# untitled.net
KiCad netlist of a schematic drawn in EAGLE
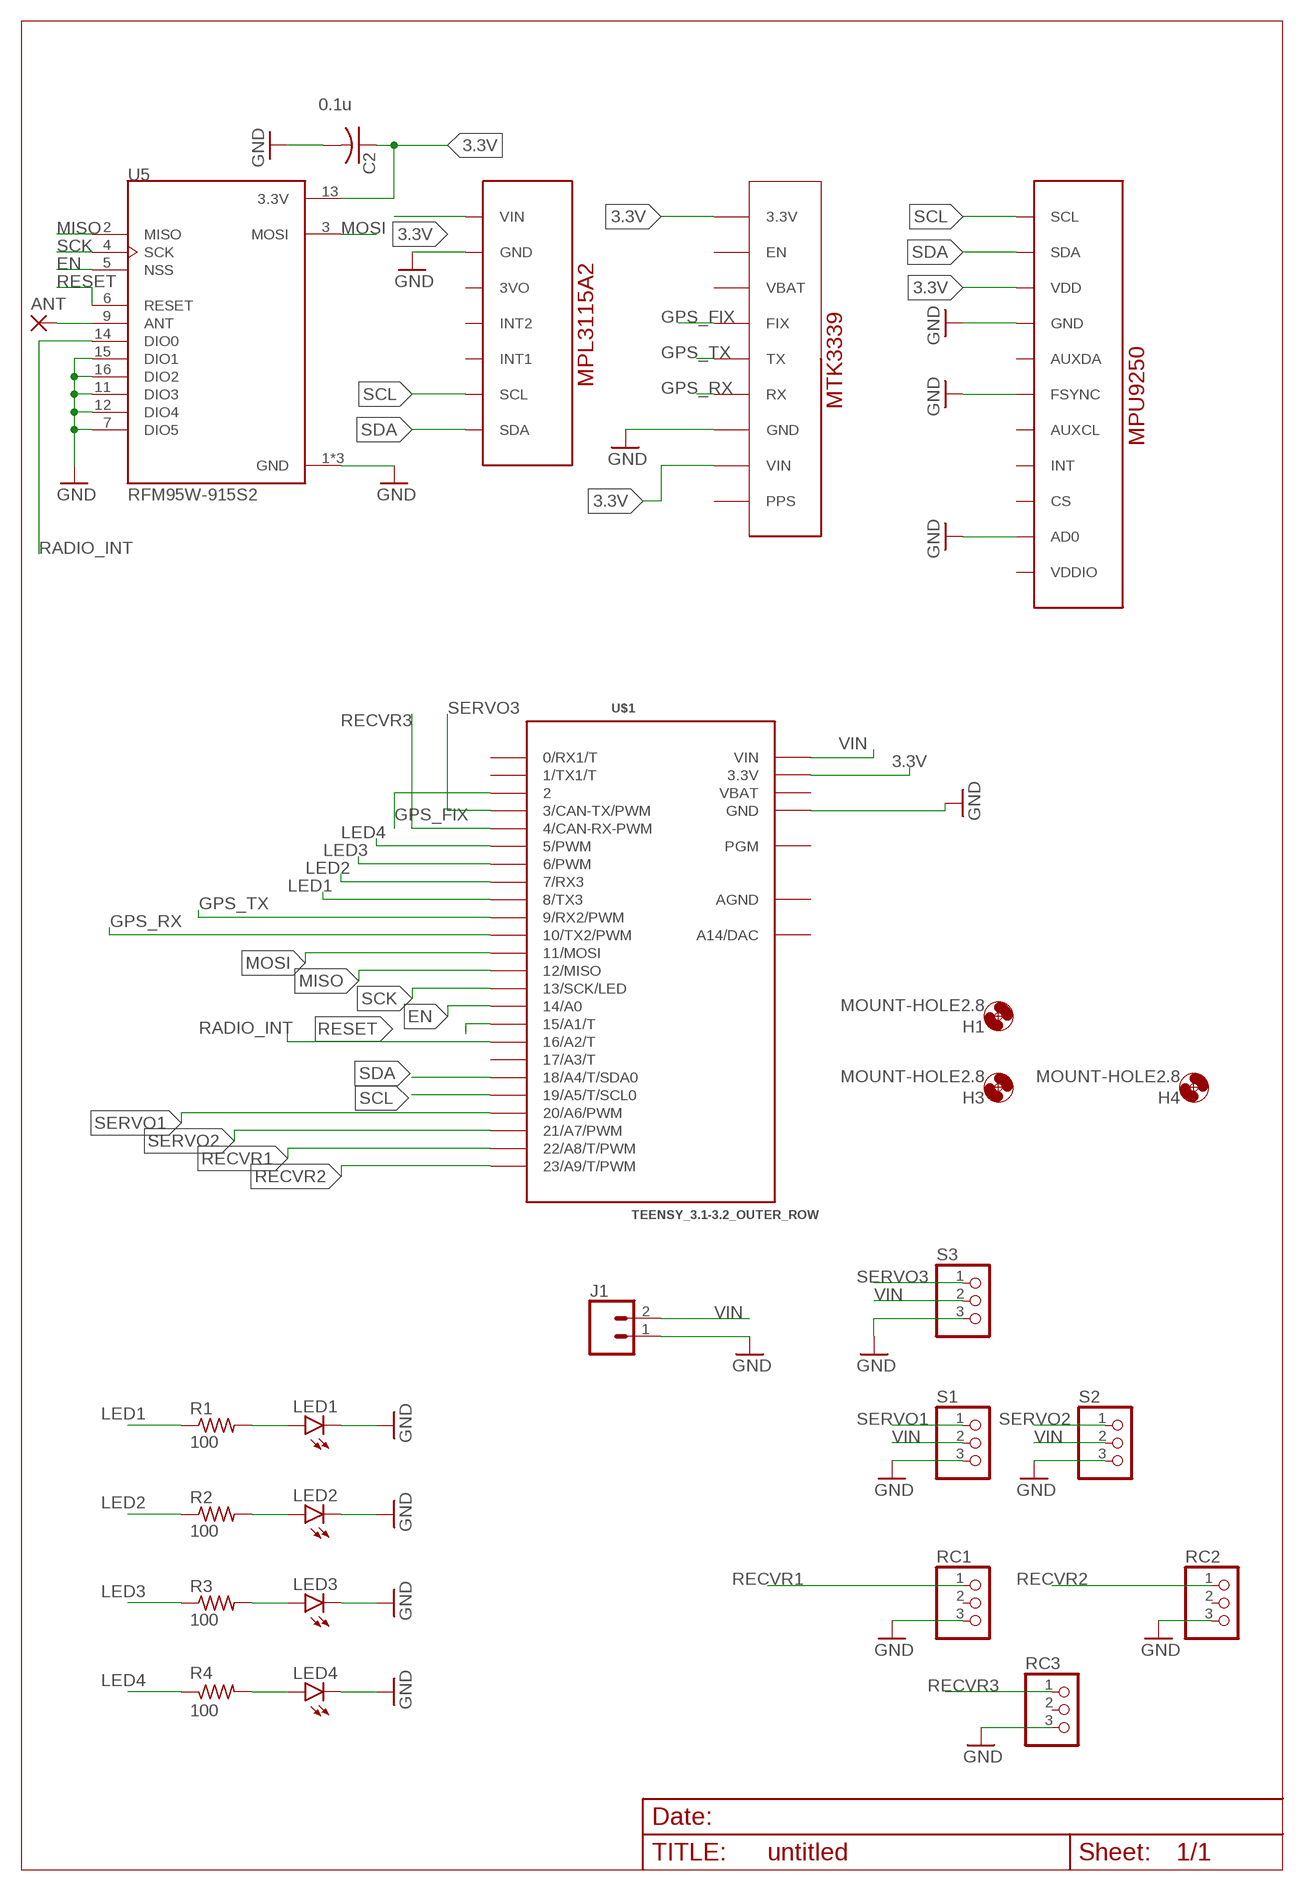
[diagram p0: schematic, sheet 1]

(export (version "E")
  (design (tool "Eeschema 10.0.6"))
  (components
    (comp (ref "ANT")
      (value "2,54/0,9")
      (footprint "eagle-import:2,54_0,9")
      (libsource (lib "eagle-import") (part "2,54/0,9"))
    )
    (comp (ref "C2")
      (value "0.1u")
      (footprint "eagle-import:C1206")
      (libsource (lib "eagle-import") (part "C-USC1206"))
    )
    (comp (ref "H1")
      (value "MOUNT-HOLE2.8")
      (footprint "eagle-import:2,8")
      (libsource (lib "eagle-import") (part "MOUNT-HOLE2.8"))
    )
    (comp (ref "H3")
      (value "MOUNT-HOLE2.8")
      (footprint "eagle-import:2,8")
      (libsource (lib "eagle-import") (part "MOUNT-HOLE2.8"))
    )
    (comp (ref "H4")
      (value "MOUNT-HOLE2.8")
      (footprint "eagle-import:2,8")
      (libsource (lib "eagle-import") (part "MOUNT-HOLE2.8"))
    )
    (comp (ref "J1")
      (value "CONN_025MM")
      (footprint "eagle-import:SCREWTERMINAL-5MM-2")
      (libsource (lib "eagle-import") (part "CONN_025MM"))
    )
    (comp (ref "LED1")
      (value "LEDCHIPLED_1206")
      (footprint "eagle-import:CHIPLED_1206")
      (libsource (lib "eagle-import") (part "LEDCHIPLED_1206"))
    )
    (comp (ref "LED2")
      (value "LEDCHIPLED_1206")
      (footprint "eagle-import:CHIPLED_1206")
      (libsource (lib "eagle-import") (part "LEDCHIPLED_1206"))
    )
    (comp (ref "LED3")
      (value "LEDCHIPLED_1206")
      (footprint "eagle-import:CHIPLED_1206")
      (libsource (lib "eagle-import") (part "LEDCHIPLED_1206"))
    )
    (comp (ref "LED4")
      (value "LEDCHIPLED_1206")
      (footprint "eagle-import:CHIPLED_1206")
      (libsource (lib "eagle-import") (part "LEDCHIPLED_1206"))
    )
    (comp (ref "R1")
      (value "100")
      (footprint "eagle-import:M1206")
      (libsource (lib "eagle-import") (part "R-US_M1206"))
    )
    (comp (ref "R2")
      (value "100")
      (footprint "eagle-import:M1206")
      (libsource (lib "eagle-import") (part "R-US_M1206"))
    )
    (comp (ref "R3")
      (value "100")
      (footprint "eagle-import:M1206")
      (libsource (lib "eagle-import") (part "R-US_M1206"))
    )
    (comp (ref "R4")
      (value "100")
      (footprint "eagle-import:M1206")
      (libsource (lib "eagle-import") (part "R-US_M1206"))
    )
    (comp (ref "RC1")
      (value "PINHD-1X3")
      (footprint "eagle-import:1X03")
      (libsource (lib "eagle-import") (part "PINHD-1X3"))
    )
    (comp (ref "RC2")
      (value "PINHD-1X3")
      (footprint "eagle-import:1X03")
      (libsource (lib "eagle-import") (part "PINHD-1X3"))
    )
    (comp (ref "RC3")
      (value "PINHD-1X3")
      (footprint "eagle-import:1X03")
      (libsource (lib "eagle-import") (part "PINHD-1X3"))
    )
    (comp (ref "S1")
      (value "PINHD-1X3")
      (footprint "eagle-import:1X03")
      (libsource (lib "eagle-import") (part "PINHD-1X3"))
    )
    (comp (ref "S2")
      (value "PINHD-1X3")
      (footprint "eagle-import:1X03")
      (libsource (lib "eagle-import") (part "PINHD-1X3"))
    )
    (comp (ref "S3")
      (value "PINHD-1X3")
      (footprint "eagle-import:1X03")
      (libsource (lib "eagle-import") (part "PINHD-1X3"))
    )
    (comp (ref "U$1")
      (value "TEENSY_3.1-3.2_OUTER_ROW")
      (footprint "eagle-import:TEENSY_3.0-3.2&LC_OUTER_ROW")
      (libsource (lib "eagle-import") (part "TEENSY_3.1-3.2_OUTER_ROW"))
    )
    (comp (ref "U1")
      (value "ADAFRUIT_MPL3115A2_BAROMETER")
      (footprint "eagle-import:ADAFRUIT_MPL3115A2_BAROMETER")
      (libsource (lib "eagle-import") (part "ADAFRUIT_MPL3115A2_BAROMETER"))
    )
    (comp (ref "U2")
      (value "ADAFRUIT_MTK3339_GPS")
      (footprint "eagle-import:ADAFRUIT_MTK3339_GPS")
      (libsource (lib "eagle-import") (part "ADAFRUIT_MTK3339_GPS"))
    )
    (comp (ref "U4")
      (value "SPARKFUN_MPU9250_IMU")
      (footprint "eagle-import:SPARKFUN_MPU9250_IMU")
      (libsource (lib "eagle-import") (part "SPARKFUN_MPU9250_IMU"))
    )
    (comp (ref "U5")
      (value "RFM95W-915S2")
      (footprint "eagle-import:XCVR_RFM95W-915S2")
      (fields (field (name "DIGI-KEY_PART_NUMBER") "RFM95W-915S2-ND") (field (name "MF") "RF Solutions"))
      (libsource (lib "eagle-import") (part "RFM95W-915S2"))
    )
  )
  (nets
    (net (code "1") (name "/AGND") (class "Default")
      (node (ref "U$1") (pin "AGND") (pinfunction "AGND_AGND") (pintype "power_in"))
    )
    (net (code "2") (name "/GPS_FIX") (class "Default")
      (node (ref "U$1") (pin "2") (pinfunction "2_2") (pintype "bidirectional"))
      (node (ref "U2") (pin "FIX") (pinfunction "FIX_FIX") (pintype "bidirectional"))
    )
    (net (code "3") (name "/GPS_RX") (class "Default")
      (node (ref "U$1") (pin "10") (pinfunction "10/TX2/PWM_10") (pintype "bidirectional"))
      (node (ref "U2") (pin "RX") (pinfunction "RX_RX") (pintype "bidirectional"))
    )
    (net (code "4") (name "/GPS_TX") (class "Default")
      (node (ref "U$1") (pin "9") (pinfunction "9/RX2/PWM_9") (pintype "bidirectional"))
      (node (ref "U2") (pin "TX") (pinfunction "TX_TX") (pintype "bidirectional"))
    )
    (net (code "5") (name "/LED1") (class "Default")
      (node (ref "R1") (pin "1") (pinfunction "1_1") (pintype "passive"))
      (node (ref "U$1") (pin "8") (pinfunction "8/TX3_8") (pintype "bidirectional"))
    )
    (net (code "6") (name "/LED2") (class "Default")
      (node (ref "R2") (pin "1") (pinfunction "1_1") (pintype "passive"))
      (node (ref "U$1") (pin "7") (pinfunction "7/RX3_7") (pintype "bidirectional"))
    )
    (net (code "7") (name "/LED3") (class "Default")
      (node (ref "R3") (pin "1") (pinfunction "1_1") (pintype "passive"))
      (node (ref "U$1") (pin "6") (pinfunction "6/PWM_6") (pintype "bidirectional"))
    )
    (net (code "8") (name "/LED4") (class "Default")
      (node (ref "R4") (pin "1") (pinfunction "1_1") (pintype "passive"))
      (node (ref "U$1") (pin "5") (pinfunction "5/PWM_5") (pintype "bidirectional"))
    )
    (net (code "9") (name "/RADIO_INT") (class "Default")
      (node (ref "U$1") (pin "16/A2") (pinfunction "16/A2/T_16/A2") (pintype "bidirectional"))
      (node (ref "U5") (pin "14") (pinfunction "DIO0_14") (pintype "bidirectional"))
    )
    (net (code "10") (name "/RECVR3") (class "Default")
      (node (ref "RC3") (pin "1") (pinfunction "1_1") (pintype "passive"))
      (node (ref "U$1") (pin "4") (pinfunction "4/CAN-RX-PWM_4") (pintype "bidirectional"))
    )
    (net (code "11") (name "/SERVO3") (class "Default")
      (node (ref "S3") (pin "1") (pinfunction "1_1") (pintype "passive"))
      (node (ref "U$1") (pin "3") (pinfunction "3/CAN-TX/PWM_3") (pintype "bidirectional"))
    )
    (net (code "12") (name "/VBAT") (class "Default")
      (node (ref "U$1") (pin "VBAT") (pinfunction "VBAT_VBAT") (pintype "power_in"))
    )
    (net (code "13") (name "/VIN") (class "Default")
      (node (ref "J1") (pin "2") (pinfunction "2_2") (pintype "passive"))
      (node (ref "S1") (pin "2") (pinfunction "2_2") (pintype "passive"))
      (node (ref "S2") (pin "2") (pinfunction "2_2") (pintype "passive"))
      (node (ref "S3") (pin "2") (pinfunction "2_2") (pintype "passive"))
      (node (ref "U$1") (pin "VIN") (pinfunction "VIN_VIN") (pintype "power_in"))
    )
    (net (code "14") (name "3.3V") (class "Default")
      (node (ref "C2") (pin "1") (pinfunction "1_1") (pintype "passive"))
      (node (ref "U$1") (pin "3.3V") (pinfunction "3.3V_3.3V") (pintype "power_in"))
      (node (ref "U$1") (pin "3.3V1") (pinfunction "3.3V_3.3V1") (pintype "power_in"))
      (node (ref "U1") (pin "VIN") (pinfunction "VIN_VIN") (pintype "bidirectional"))
      (node (ref "U2") (pin "3.3V") (pinfunction "3.3V_3.3V") (pintype "bidirectional"))
      (node (ref "U2") (pin "VIN") (pinfunction "VIN_VIN") (pintype "bidirectional"))
      (node (ref "U4") (pin "VDD") (pinfunction "VDD_VDD") (pintype "bidirectional"))
      (node (ref "U5") (pin "13") (pinfunction "3.3V_13") (pintype "power_in"))
    )
    (net (code "15") (name "EN") (class "Default")
      (node (ref "U$1") (pin "14/A0") (pinfunction "14/A0_14/A0") (pintype "bidirectional"))
      (node (ref "U5") (pin "5") (pinfunction "NSS_5") (pintype "input"))
    )
    (net (code "16") (name "GND") (class "Default")
      (node (ref "C2") (pin "2") (pinfunction "2_2") (pintype "passive"))
      (node (ref "J1") (pin "1") (pinfunction "1_1") (pintype "passive"))
      (node (ref "LED1") (pin "C") (pinfunction "C_C") (pintype "passive"))
      (node (ref "LED2") (pin "C") (pinfunction "C_C") (pintype "passive"))
      (node (ref "LED3") (pin "C") (pinfunction "C_C") (pintype "passive"))
      (node (ref "LED4") (pin "C") (pinfunction "C_C") (pintype "passive"))
      (node (ref "RC1") (pin "3") (pinfunction "3_3") (pintype "passive"))
      (node (ref "RC2") (pin "3") (pinfunction "3_3") (pintype "passive"))
      (node (ref "RC3") (pin "3") (pinfunction "3_3") (pintype "passive"))
      (node (ref "S1") (pin "3") (pinfunction "3_3") (pintype "passive"))
      (node (ref "S2") (pin "3") (pinfunction "3_3") (pintype "passive"))
      (node (ref "S3") (pin "3") (pinfunction "3_3") (pintype "passive"))
      (node (ref "U$1") (pin "GND") (pinfunction "GND_GND") (pintype "power_in"))
      (node (ref "U$1") (pin "GND1") (pinfunction "GND_GND1") (pintype "power_in"))
      (node (ref "U1") (pin "GND") (pinfunction "GND_GND") (pintype "bidirectional"))
      (node (ref "U2") (pin "GND") (pinfunction "GND_GND") (pintype "bidirectional"))
      (node (ref "U4") (pin "AD0") (pinfunction "AD0_AD0") (pintype "bidirectional"))
      (node (ref "U4") (pin "FSYNC") (pinfunction "FSYNC_FSYNC") (pintype "bidirectional"))
      (node (ref "U4") (pin "GND") (pinfunction "GND_GND") (pintype "bidirectional"))
      (node (ref "U5") (pin "1") (pinfunction "GND_1") (pintype "power_in"))
      (node (ref "U5") (pin "10") (pinfunction "GND_10") (pintype "power_in"))
      (node (ref "U5") (pin "11") (pinfunction "DIO3_11") (pintype "bidirectional"))
      (node (ref "U5") (pin "12") (pinfunction "DIO4_12") (pintype "bidirectional"))
      (node (ref "U5") (pin "15") (pinfunction "DIO1_15") (pintype "bidirectional"))
      (node (ref "U5") (pin "16") (pinfunction "DIO2_16") (pintype "bidirectional"))
      (node (ref "U5") (pin "7") (pinfunction "DIO5_7") (pintype "bidirectional"))
      (node (ref "U5") (pin "8") (pinfunction "GND_8") (pintype "power_in"))
    )
    (net (code "17") (name "MISO") (class "Default")
      (node (ref "U$1") (pin "12") (pinfunction "12/MISO_12") (pintype "bidirectional"))
      (node (ref "U5") (pin "2") (pinfunction "MISO_2") (pintype "input"))
    )
    (net (code "18") (name "MOSI") (class "Default")
      (node (ref "U$1") (pin "11") (pinfunction "11/MOSI_11") (pintype "bidirectional"))
      (node (ref "U5") (pin "3") (pinfunction "MOSI_3") (pintype "output"))
    )
    (net (code "19") (name "Net-(ANT-P)") (class "Default")
      (node (ref "ANT") (pin "1") (pinfunction "P_1") (pintype "passive"))
      (node (ref "U5") (pin "9") (pinfunction "ANT_9") (pintype "bidirectional"))
    )
    (net (code "20") (name "Net-(LED1-PadA)") (class "Default")
      (node (ref "LED1") (pin "A") (pinfunction "A_A") (pintype "passive"))
      (node (ref "R1") (pin "2") (pinfunction "2_2") (pintype "passive"))
    )
    (net (code "21") (name "Net-(LED2-PadA)") (class "Default")
      (node (ref "LED2") (pin "A") (pinfunction "A_A") (pintype "passive"))
      (node (ref "R2") (pin "2") (pinfunction "2_2") (pintype "passive"))
    )
    (net (code "22") (name "Net-(LED3-PadA)") (class "Default")
      (node (ref "LED3") (pin "A") (pinfunction "A_A") (pintype "passive"))
      (node (ref "R3") (pin "2") (pinfunction "2_2") (pintype "passive"))
    )
    (net (code "23") (name "Net-(LED4-PadA)") (class "Default")
      (node (ref "LED4") (pin "A") (pinfunction "A_A") (pintype "passive"))
      (node (ref "R4") (pin "2") (pinfunction "2_2") (pintype "passive"))
    )
    (net (code "24") (name "RECVR1") (class "Default")
      (node (ref "RC1") (pin "1") (pinfunction "1_1") (pintype "passive"))
      (node (ref "U$1") (pin "22/A8") (pinfunction "22/A8/T/PWM_22/A8") (pintype "bidirectional"))
    )
    (net (code "25") (name "RECVR2") (class "Default")
      (node (ref "RC2") (pin "1") (pinfunction "1_1") (pintype "passive"))
      (node (ref "U$1") (pin "23/A9") (pinfunction "23/A9/T/PWM_23/A9") (pintype "bidirectional"))
    )
    (net (code "26") (name "RESET") (class "Default")
      (node (ref "U$1") (pin "15/A1") (pinfunction "15/A1/T_15/A1") (pintype "bidirectional"))
      (node (ref "U5") (pin "6") (pinfunction "RESET_6") (pintype "bidirectional"))
    )
    (net (code "27") (name "SCK") (class "Default")
      (node (ref "U$1") (pin "13") (pinfunction "13/SCK/LED_13") (pintype "bidirectional"))
      (node (ref "U5") (pin "4") (pinfunction "SCK_4") (pintype "input"))
    )
    (net (code "28") (name "SCL") (class "Default")
      (node (ref "U$1") (pin "19/A5") (pinfunction "19/A5/T/SCL0_19/A5") (pintype "bidirectional"))
      (node (ref "U1") (pin "SCL") (pinfunction "SCL_SCL") (pintype "bidirectional"))
      (node (ref "U4") (pin "SCL") (pinfunction "SCL_SCL") (pintype "bidirectional"))
    )
    (net (code "29") (name "SDA") (class "Default")
      (node (ref "U$1") (pin "18/A4") (pinfunction "18/A4/T/SDA0_18/A4") (pintype "bidirectional"))
      (node (ref "U1") (pin "SDA") (pinfunction "SDA_SDA") (pintype "bidirectional"))
      (node (ref "U4") (pin "SDA") (pinfunction "SDA_SDA") (pintype "bidirectional"))
    )
    (net (code "30") (name "SERVO1") (class "Default")
      (node (ref "S1") (pin "1") (pinfunction "1_1") (pintype "passive"))
      (node (ref "U$1") (pin "20/A6") (pinfunction "20/A6/PWM_20/A6") (pintype "bidirectional"))
    )
    (net (code "31") (name "SERVO2") (class "Default")
      (node (ref "S2") (pin "1") (pinfunction "1_1") (pintype "passive"))
      (node (ref "U$1") (pin "21/A7") (pinfunction "21/A7/PWM_21/A7") (pintype "bidirectional"))
    )
    (net (code "32") (name "unconnected-(RC1-Pad2)") (class "Default")
      (node (ref "RC1") (pin "2") (pinfunction "2_2") (pintype "passive"))
    )
    (net (code "33") (name "unconnected-(RC2-Pad2)") (class "Default")
      (node (ref "RC2") (pin "2") (pinfunction "2_2") (pintype "passive"))
    )
    (net (code "34") (name "unconnected-(RC3-Pad2)") (class "Default")
      (node (ref "RC3") (pin "2") (pinfunction "2_2") (pintype "passive"))
    )
    (net (code "35") (name "unconnected-(U$1-0{slash}RX1{slash}T-Pad0)") (class "Default")
      (node (ref "U$1") (pin "0") (pinfunction "0/RX1/T_0") (pintype "bidirectional"))
    )
    (net (code "36") (name "unconnected-(U$1-1{slash}TX1{slash}T-Pad1)") (class "Default")
      (node (ref "U$1") (pin "1") (pinfunction "1/TX1/T_1") (pintype "bidirectional"))
    )
    (net (code "37") (name "unconnected-(U$1-17{slash}A3{slash}T-Pad17{slash}A3)") (class "Default")
      (node (ref "U$1") (pin "17/A3") (pinfunction "17/A3/T_17/A3") (pintype "bidirectional"))
    )
    (net (code "38") (name "unconnected-(U$1-A14{slash}DAC-PadRESET{slash}DAC)") (class "Default")
      (node (ref "U$1") (pin "RESET/DAC") (pinfunction "A14/DAC_RESET/DAC") (pintype "bidirectional"))
    )
    (net (code "39") (name "unconnected-(U$1-PadPGM)") (class "Default")
      (node (ref "U$1") (pin "PGM") (pinfunction "PGM_PGM") (pintype "bidirectional"))
    )
    (net (code "40") (name "unconnected-(U1-Pad3VO)") (class "Default")
      (node (ref "U1") (pin "3VO") (pinfunction "3VO_3VO") (pintype "bidirectional"))
    )
    (net (code "41") (name "unconnected-(U1-PadINT1)") (class "Default")
      (node (ref "U1") (pin "INT1") (pinfunction "INT1_INT1") (pintype "bidirectional"))
    )
    (net (code "42") (name "unconnected-(U1-PadINT2)") (class "Default")
      (node (ref "U1") (pin "INT2") (pinfunction "INT2_INT2") (pintype "bidirectional"))
    )
    (net (code "43") (name "unconnected-(U2-PadEN)") (class "Default")
      (node (ref "U2") (pin "EN") (pinfunction "EN_EN") (pintype "bidirectional"))
    )
    (net (code "44") (name "unconnected-(U2-PadPPS)") (class "Default")
      (node (ref "U2") (pin "PPS") (pinfunction "PPS_PPS") (pintype "bidirectional"))
    )
    (net (code "45") (name "unconnected-(U2-PadVBAT)") (class "Default")
      (node (ref "U2") (pin "VBAT") (pinfunction "VBAT_VBAT") (pintype "bidirectional"))
    )
    (net (code "46") (name "unconnected-(U4-PadAUXCL)") (class "Default")
      (node (ref "U4") (pin "AUXCL") (pinfunction "AUXCL_AUXCL") (pintype "bidirectional"))
    )
    (net (code "47") (name "unconnected-(U4-PadAUXDA)") (class "Default")
      (node (ref "U4") (pin "AUXDA") (pinfunction "AUXDA_AUXDA") (pintype "bidirectional"))
    )
    (net (code "48") (name "unconnected-(U4-PadCS)") (class "Default")
      (node (ref "U4") (pin "CS") (pinfunction "CS_CS") (pintype "bidirectional"))
    )
    (net (code "49") (name "unconnected-(U4-PadINT)") (class "Default")
      (node (ref "U4") (pin "INT") (pinfunction "INT_INT") (pintype "bidirectional"))
    )
    (net (code "50") (name "unconnected-(U4-PadVDDIO)") (class "Default")
      (node (ref "U4") (pin "VDDIO") (pinfunction "VDDIO_VDDIO") (pintype "bidirectional"))
    )
  )
)
